# feedback.net
KiCad netlist of a schematic drawn in Altium Designer
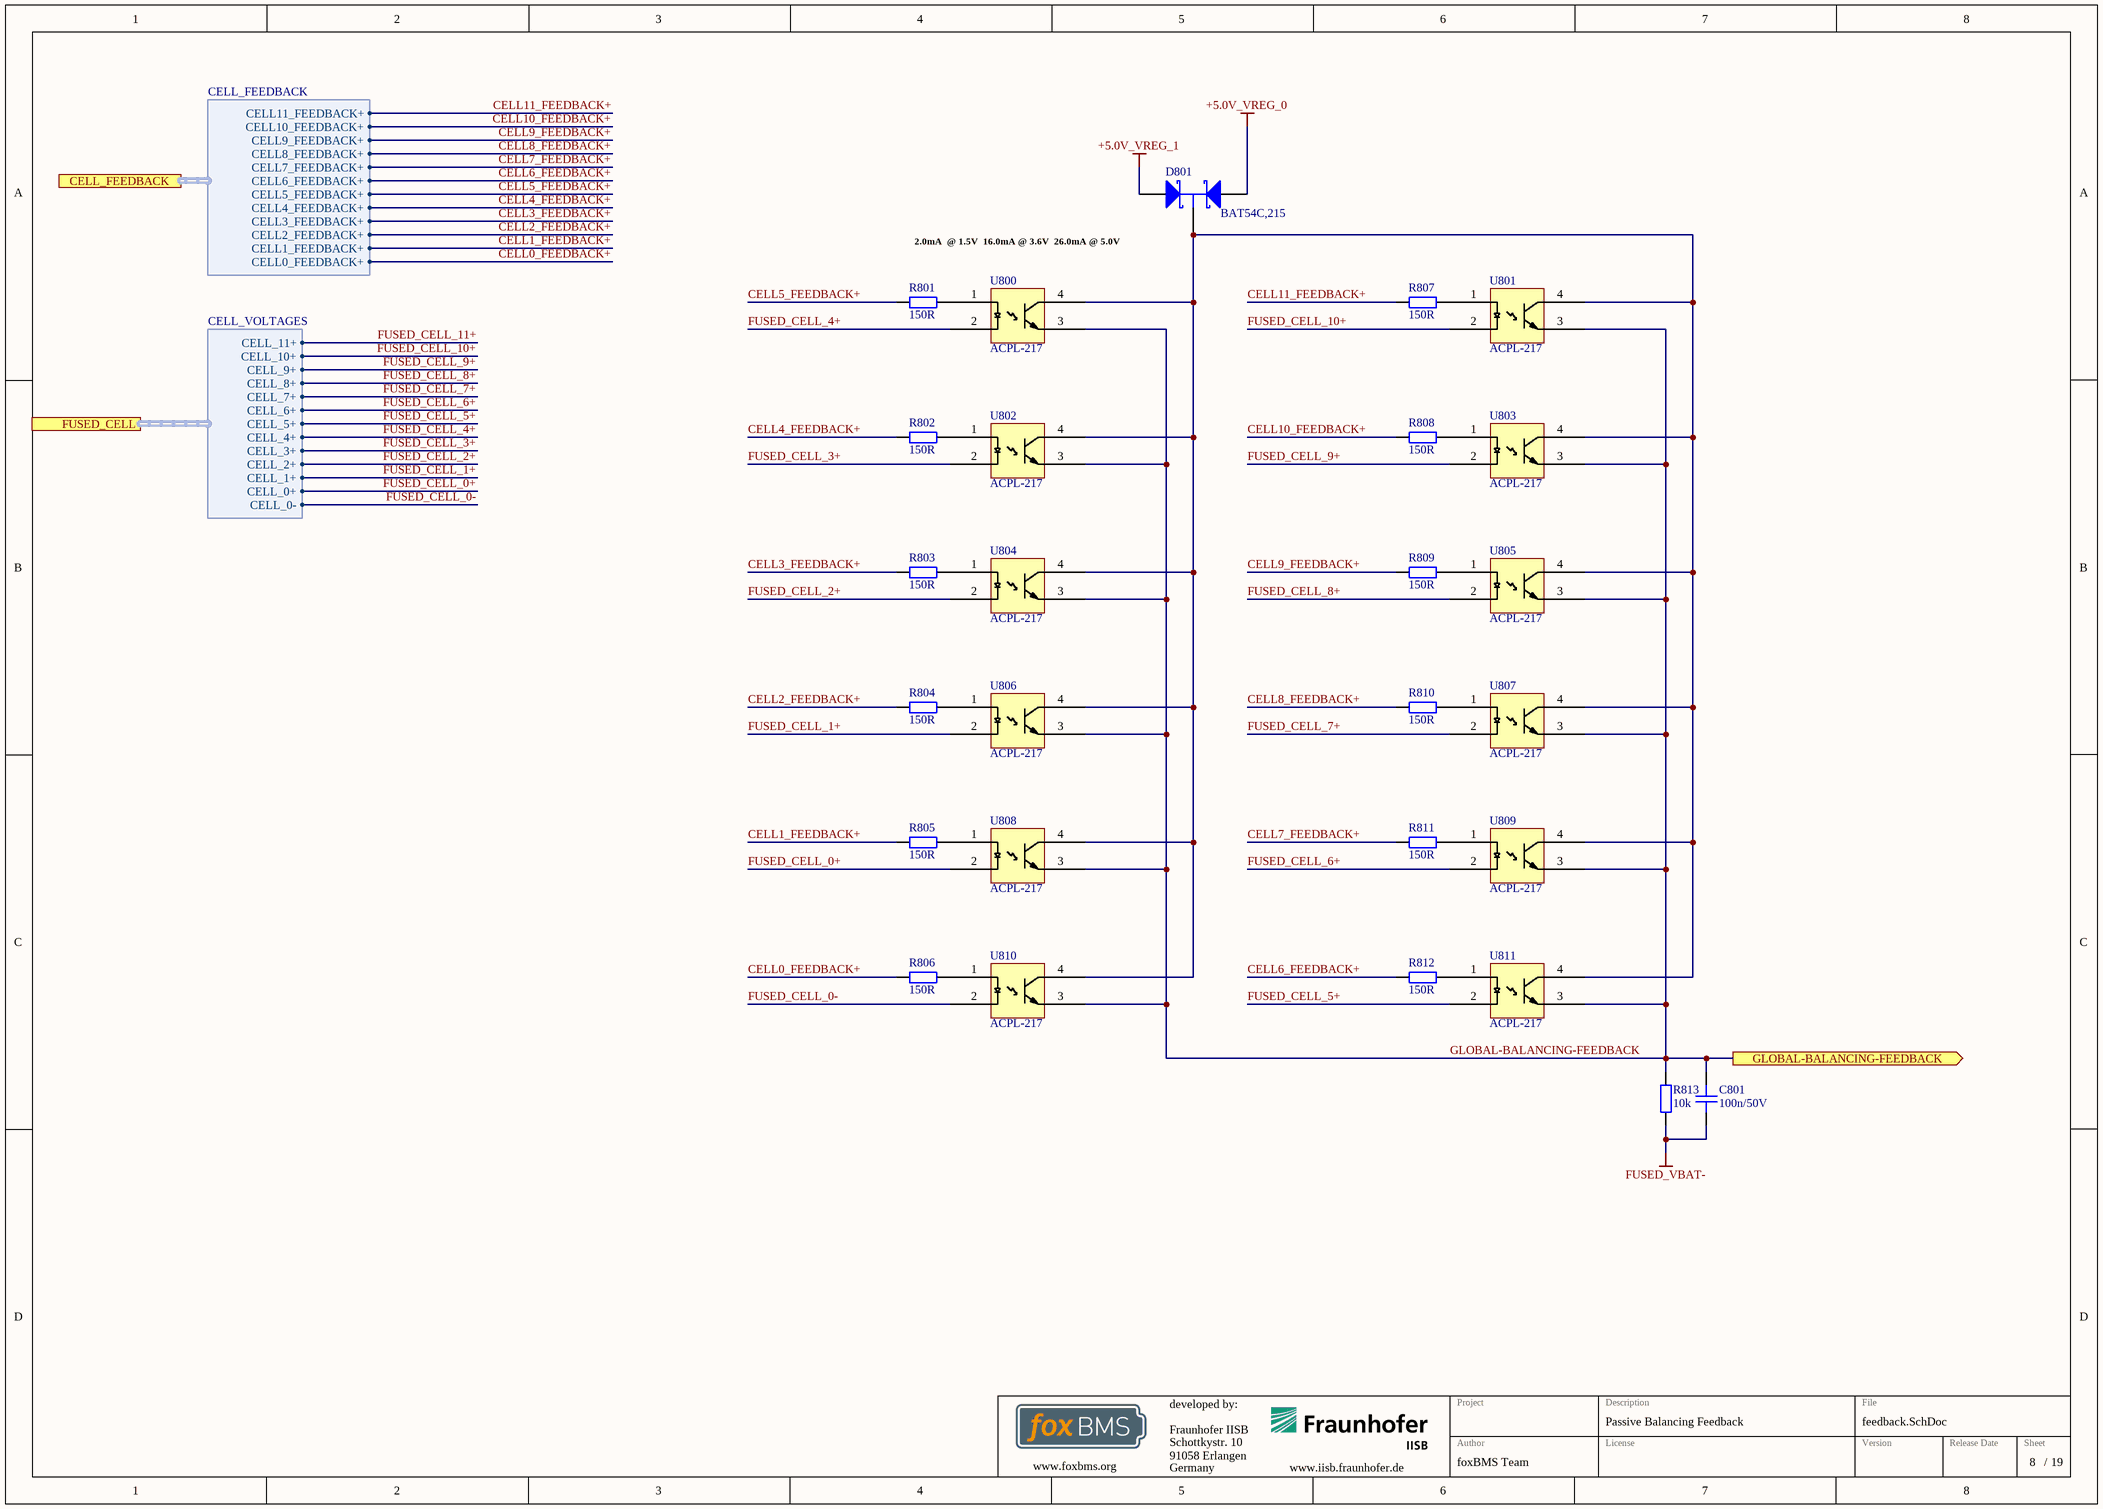
[diagram p0: feedback.SchDoc]

(export (version "E")
  (design (tool "Eeschema 10.0.6"))
  (components
    (comp (ref "C801")
      (value "100n/50V")
      (footprint "CAPC1608X08N")
      (description "MLCC")
      (fields (field (name "PART NUMBER") "gen_C_ceramic_100n_50V_X7R_0603"))
      (libsource (lib "OE750") (part "C"))
    )
    (comp (ref "D801")
      (value "BAT54C,215")
      (footprint "NXP-SOT23-3_V")
      (description "Schottky Barrier Diode, 30 V, 3-Pin SOT23, RoHS, Tape and Reel")
      (fields (field (name "MANUFACTURER") "NXP Semiconductors"))
      (libsource (lib "Altium Content Vault") (part "DSKY-AAK-3"))
    )
    (comp (ref "R801")
      (value "150R")
      (footprint "RESC1608X05N")
      (description "SMD Resistor 150R 0603")
      (fields (field (name "PART NUMBER") "gen_R_150R_0603") (field (name "TOLERANCE") "1%"))
      (libsource (lib "OE750") (part "R"))
    )
    (comp (ref "R802")
      (value "150R")
      (footprint "RESC1608X05N")
      (description "SMD Resistor 150R 0603")
      (fields (field (name "PART NUMBER") "gen_R_150R_0603") (field (name "TOLERANCE") "1%"))
      (libsource (lib "OE750") (part "R"))
    )
    (comp (ref "R803")
      (value "150R")
      (footprint "RESC1608X05N")
      (description "SMD Resistor 150R 0603")
      (fields (field (name "PART NUMBER") "gen_R_150R_0603") (field (name "TOLERANCE") "1%"))
      (libsource (lib "OE750") (part "R"))
    )
    (comp (ref "R804")
      (value "150R")
      (footprint "RESC1608X05N")
      (description "SMD Resistor 150R 0603")
      (fields (field (name "PART NUMBER") "gen_R_150R_0603") (field (name "TOLERANCE") "1%"))
      (libsource (lib "OE750") (part "R"))
    )
    (comp (ref "R805")
      (value "150R")
      (footprint "RESC1608X05N")
      (description "SMD Resistor 150R 0603")
      (fields (field (name "PART NUMBER") "gen_R_150R_0603") (field (name "TOLERANCE") "1%"))
      (libsource (lib "OE750") (part "R"))
    )
    (comp (ref "R806")
      (value "150R")
      (footprint "RESC1608X05N")
      (description "SMD Resistor 150R 0603")
      (fields (field (name "PART NUMBER") "gen_R_150R_0603") (field (name "TOLERANCE") "1%"))
      (libsource (lib "OE750") (part "R"))
    )
    (comp (ref "R807")
      (value "150R")
      (footprint "RESC1608X05N")
      (description "SMD Resistor 150R 0603")
      (fields (field (name "PART NUMBER") "gen_R_150R_0603") (field (name "TOLERANCE") "1%"))
      (libsource (lib "OE750") (part "R"))
    )
    (comp (ref "R808")
      (value "150R")
      (footprint "RESC1608X05N")
      (description "SMD Resistor 150R 0603")
      (fields (field (name "PART NUMBER") "gen_R_150R_0603") (field (name "TOLERANCE") "1%"))
      (libsource (lib "OE750") (part "R"))
    )
    (comp (ref "R809")
      (value "150R")
      (footprint "RESC1608X05N")
      (description "SMD Resistor 150R 0603")
      (fields (field (name "PART NUMBER") "gen_R_150R_0603") (field (name "TOLERANCE") "1%"))
      (libsource (lib "OE750") (part "R"))
    )
    (comp (ref "R810")
      (value "150R")
      (footprint "RESC1608X05N")
      (description "SMD Resistor 150R 0603")
      (fields (field (name "PART NUMBER") "gen_R_150R_0603") (field (name "TOLERANCE") "1%"))
      (libsource (lib "OE750") (part "R"))
    )
    (comp (ref "R811")
      (value "150R")
      (footprint "RESC1608X05N")
      (description "SMD Resistor 150R 0603")
      (fields (field (name "PART NUMBER") "gen_R_150R_0603") (field (name "TOLERANCE") "1%"))
      (libsource (lib "OE750") (part "R"))
    )
    (comp (ref "R812")
      (value "150R")
      (footprint "RESC1608X05N")
      (description "SMD Resistor 150R 0603")
      (fields (field (name "PART NUMBER") "gen_R_150R_0603") (field (name "TOLERANCE") "1%"))
      (libsource (lib "OE750") (part "R"))
    )
    (comp (ref "R813")
      (value "10k")
      (footprint "RESC1608X05N")
      (description "SMD Resistor 10k 0603")
      (fields (field (name "PART NUMBER") "gen_R_10k_0603") (field (name "TOLERANCE") "1%"))
      (libsource (lib "OE750") (part "R"))
    )
    (comp (ref "U800")
      (value "ACPL-217")
      (footprint "SOIC127P700X220-4N")
      (description "Optocoupler, Transistor Output, 1 Channel")
      (fields (field (name "PART NUMBER") "ACPL-217-56BE") (field (name "MANUFACTURER") "Broadcom Limited"))
      (libsource (lib "OE750") (part "ACPL-217"))
    )
    (comp (ref "U801")
      (value "ACPL-217")
      (footprint "SOIC127P700X220-4N")
      (description "Optocoupler, Transistor Output, 1 Channel")
      (fields (field (name "PART NUMBER") "ACPL-217-56BE") (field (name "MANUFACTURER") "Broadcom Limited"))
      (libsource (lib "OE750") (part "ACPL-217"))
    )
    (comp (ref "U802")
      (value "ACPL-217")
      (footprint "SOIC127P700X220-4N")
      (description "Optocoupler, Transistor Output, 1 Channel")
      (fields (field (name "PART NUMBER") "ACPL-217-56BE") (field (name "MANUFACTURER") "Broadcom Limited"))
      (libsource (lib "OE750") (part "ACPL-217"))
    )
    (comp (ref "U803")
      (value "ACPL-217")
      (footprint "SOIC127P700X220-4N")
      (description "Optocoupler, Transistor Output, 1 Channel")
      (fields (field (name "PART NUMBER") "ACPL-217-56BE") (field (name "MANUFACTURER") "Broadcom Limited"))
      (libsource (lib "OE750") (part "ACPL-217"))
    )
    (comp (ref "U804")
      (value "ACPL-217")
      (footprint "SOIC127P700X220-4N")
      (description "Optocoupler, Transistor Output, 1 Channel")
      (fields (field (name "PART NUMBER") "ACPL-217-56BE") (field (name "MANUFACTURER") "Broadcom Limited"))
      (libsource (lib "OE750") (part "ACPL-217"))
    )
    (comp (ref "U805")
      (value "ACPL-217")
      (footprint "SOIC127P700X220-4N")
      (description "Optocoupler, Transistor Output, 1 Channel")
      (fields (field (name "PART NUMBER") "ACPL-217-56BE") (field (name "MANUFACTURER") "Broadcom Limited"))
      (libsource (lib "OE750") (part "ACPL-217"))
    )
    (comp (ref "U806")
      (value "ACPL-217")
      (footprint "SOIC127P700X220-4N")
      (description "Optocoupler, Transistor Output, 1 Channel")
      (fields (field (name "PART NUMBER") "ACPL-217-56BE") (field (name "MANUFACTURER") "Broadcom Limited"))
      (libsource (lib "OE750") (part "ACPL-217"))
    )
    (comp (ref "U807")
      (value "ACPL-217")
      (footprint "SOIC127P700X220-4N")
      (description "Optocoupler, Transistor Output, 1 Channel")
      (fields (field (name "PART NUMBER") "ACPL-217-56BE") (field (name "MANUFACTURER") "Broadcom Limited"))
      (libsource (lib "OE750") (part "ACPL-217"))
    )
    (comp (ref "U808")
      (value "ACPL-217")
      (footprint "SOIC127P700X220-4N")
      (description "Optocoupler, Transistor Output, 1 Channel")
      (fields (field (name "PART NUMBER") "ACPL-217-56BE") (field (name "MANUFACTURER") "Broadcom Limited"))
      (libsource (lib "OE750") (part "ACPL-217"))
    )
    (comp (ref "U809")
      (value "ACPL-217")
      (footprint "SOIC127P700X220-4N")
      (description "Optocoupler, Transistor Output, 1 Channel")
      (fields (field (name "PART NUMBER") "ACPL-217-56BE") (field (name "MANUFACTURER") "Broadcom Limited"))
      (libsource (lib "OE750") (part "ACPL-217"))
    )
    (comp (ref "U810")
      (value "ACPL-217")
      (footprint "SOIC127P700X220-4N")
      (description "Optocoupler, Transistor Output, 1 Channel")
      (fields (field (name "PART NUMBER") "ACPL-217-56BE") (field (name "MANUFACTURER") "Broadcom Limited"))
      (libsource (lib "OE750") (part "ACPL-217"))
    )
    (comp (ref "U811")
      (value "ACPL-217")
      (footprint "SOIC127P700X220-4N")
      (description "Optocoupler, Transistor Output, 1 Channel")
      (fields (field (name "PART NUMBER") "ACPL-217-56BE") (field (name "MANUFACTURER") "Broadcom Limited"))
      (libsource (lib "OE750") (part "ACPL-217"))
    )
  )
  (nets
    (net (code "3") (name "+5.0V_VREG_0") (class "Default")
      (node (ref "D801") (pin "2") (pinfunction "A_2") (pintype "passive"))
    )
    (net (code "4") (name "+5.0V_VREG_1") (class "Default")
      (node (ref "D801") (pin "1") (pinfunction "A_1") (pintype "passive"))
    )
    (net (code "5") (name "/CELL0_FEEDBACK+") (class "Default")
      (node (ref "R806") (pin "1") (pinfunction "1_1") (pintype "passive"))
    )
    (net (code "6") (name "/CELL1_FEEDBACK+") (class "Default")
      (node (ref "R805") (pin "1") (pinfunction "1_1") (pintype "passive"))
    )
    (net (code "7") (name "/CELL2_FEEDBACK+") (class "Default")
      (node (ref "R804") (pin "1") (pinfunction "1_1") (pintype "passive"))
    )
    (net (code "8") (name "/CELL3_FEEDBACK+") (class "Default")
      (node (ref "R803") (pin "1") (pinfunction "1_1") (pintype "passive"))
    )
    (net (code "9") (name "/CELL4_FEEDBACK+") (class "Default")
      (node (ref "R802") (pin "1") (pinfunction "1_1") (pintype "passive"))
    )
    (net (code "10") (name "/CELL5_FEEDBACK+") (class "Default")
      (node (ref "R801") (pin "1") (pinfunction "1_1") (pintype "passive"))
    )
    (net (code "11") (name "/CELL6_FEEDBACK+") (class "Default")
      (node (ref "R812") (pin "1") (pinfunction "1_1") (pintype "passive"))
    )
    (net (code "12") (name "/CELL7_FEEDBACK+") (class "Default")
      (node (ref "R811") (pin "1") (pinfunction "1_1") (pintype "passive"))
    )
    (net (code "13") (name "/CELL8_FEEDBACK+") (class "Default")
      (node (ref "R810") (pin "1") (pinfunction "1_1") (pintype "passive"))
    )
    (net (code "14") (name "/CELL9_FEEDBACK+") (class "Default")
      (node (ref "R809") (pin "1") (pinfunction "1_1") (pintype "passive"))
    )
    (net (code "15") (name "/CELL10_FEEDBACK+") (class "Default")
      (node (ref "R808") (pin "1") (pinfunction "1_1") (pintype "passive"))
    )
    (net (code "16") (name "/CELL11_FEEDBACK+") (class "Default")
      (node (ref "R807") (pin "1") (pinfunction "1_1") (pintype "passive"))
    )
    (net (code "17") (name "/FUSED_CELL_0+") (class "Default")
      (node (ref "U808") (pin "2") (pintype "power_in"))
    )
    (net (code "18") (name "/FUSED_CELL_0-") (class "Default")
      (node (ref "U810") (pin "2") (pintype "power_in"))
    )
    (net (code "19") (name "/FUSED_CELL_1+") (class "Default")
      (node (ref "U806") (pin "2") (pintype "power_in"))
    )
    (net (code "20") (name "/FUSED_CELL_2+") (class "Default")
      (node (ref "U804") (pin "2") (pintype "power_in"))
    )
    (net (code "21") (name "/FUSED_CELL_3+") (class "Default")
      (node (ref "U802") (pin "2") (pintype "power_in"))
    )
    (net (code "22") (name "/FUSED_CELL_4+") (class "Default")
      (node (ref "U800") (pin "2") (pintype "power_in"))
    )
    (net (code "23") (name "/FUSED_CELL_5+") (class "Default")
      (node (ref "U811") (pin "2") (pintype "power_in"))
    )
    (net (code "24") (name "/FUSED_CELL_6+") (class "Default")
      (node (ref "U809") (pin "2") (pintype "power_in"))
    )
    (net (code "25") (name "/FUSED_CELL_7+") (class "Default")
      (node (ref "U807") (pin "2") (pintype "power_in"))
    )
    (net (code "26") (name "/FUSED_CELL_8+") (class "Default")
      (node (ref "U805") (pin "2") (pintype "power_in"))
    )
    (net (code "27") (name "/FUSED_CELL_9+") (class "Default")
      (node (ref "U803") (pin "2") (pintype "power_in"))
    )
    (net (code "28") (name "/FUSED_CELL_10+") (class "Default")
      (node (ref "U801") (pin "2") (pintype "power_in"))
    )
    (net (code "30") (name "/GLOBAL-BALANCING-FEEDBACK") (class "Default")
      (node (ref "C801") (pin "2") (pinfunction "2_2") (pintype "passive"))
      (node (ref "R813") (pin "1") (pinfunction "1_1") (pintype "passive"))
      (node (ref "U800") (pin "3") (pintype "passive"))
      (node (ref "U801") (pin "3") (pintype "passive"))
      (node (ref "U802") (pin "3") (pintype "passive"))
      (node (ref "U803") (pin "3") (pintype "passive"))
      (node (ref "U804") (pin "3") (pintype "passive"))
      (node (ref "U805") (pin "3") (pintype "passive"))
      (node (ref "U806") (pin "3") (pintype "passive"))
      (node (ref "U807") (pin "3") (pintype "passive"))
      (node (ref "U808") (pin "3") (pintype "passive"))
      (node (ref "U809") (pin "3") (pintype "passive"))
      (node (ref "U810") (pin "3") (pintype "passive"))
      (node (ref "U811") (pin "3") (pintype "passive"))
    )
    (net (code "33") (name "FUSED_VBAT-") (class "Default")
      (node (ref "C801") (pin "1") (pinfunction "1_1") (pintype "passive"))
      (node (ref "R813") (pin "2") (pinfunction "2_2") (pintype "passive"))
    )
    (net (code "34") (name "Net-(D801-K)") (class "Default")
      (node (ref "D801") (pin "3") (pinfunction "K_3") (pintype "passive"))
      (node (ref "U800") (pin "4") (pintype "passive"))
      (node (ref "U801") (pin "4") (pintype "passive"))
      (node (ref "U802") (pin "4") (pintype "passive"))
      (node (ref "U803") (pin "4") (pintype "passive"))
      (node (ref "U804") (pin "4") (pintype "passive"))
      (node (ref "U805") (pin "4") (pintype "passive"))
      (node (ref "U806") (pin "4") (pintype "passive"))
      (node (ref "U807") (pin "4") (pintype "passive"))
      (node (ref "U808") (pin "4") (pintype "passive"))
      (node (ref "U809") (pin "4") (pintype "passive"))
      (node (ref "U810") (pin "4") (pintype "passive"))
      (node (ref "U811") (pin "4") (pintype "passive"))
    )
    (net (code "35") (name "Net-(R801-Pad2)") (class "Default")
      (node (ref "R801") (pin "2") (pinfunction "2_2") (pintype "passive"))
      (node (ref "U800") (pin "1") (pintype "passive"))
    )
    (net (code "36") (name "Net-(R802-Pad2)") (class "Default")
      (node (ref "R802") (pin "2") (pinfunction "2_2") (pintype "passive"))
      (node (ref "U802") (pin "1") (pintype "passive"))
    )
    (net (code "37") (name "Net-(R803-Pad2)") (class "Default")
      (node (ref "R803") (pin "2") (pinfunction "2_2") (pintype "passive"))
      (node (ref "U804") (pin "1") (pintype "passive"))
    )
    (net (code "38") (name "Net-(R804-Pad2)") (class "Default")
      (node (ref "R804") (pin "2") (pinfunction "2_2") (pintype "passive"))
      (node (ref "U806") (pin "1") (pintype "passive"))
    )
    (net (code "39") (name "Net-(R805-Pad2)") (class "Default")
      (node (ref "R805") (pin "2") (pinfunction "2_2") (pintype "passive"))
      (node (ref "U808") (pin "1") (pintype "passive"))
    )
    (net (code "40") (name "Net-(R806-Pad2)") (class "Default")
      (node (ref "R806") (pin "2") (pinfunction "2_2") (pintype "passive"))
      (node (ref "U810") (pin "1") (pintype "passive"))
    )
    (net (code "41") (name "Net-(R807-Pad2)") (class "Default")
      (node (ref "R807") (pin "2") (pinfunction "2_2") (pintype "passive"))
      (node (ref "U801") (pin "1") (pintype "passive"))
    )
    (net (code "42") (name "Net-(R808-Pad2)") (class "Default")
      (node (ref "R808") (pin "2") (pinfunction "2_2") (pintype "passive"))
      (node (ref "U803") (pin "1") (pintype "passive"))
    )
    (net (code "43") (name "Net-(R809-Pad2)") (class "Default")
      (node (ref "R809") (pin "2") (pinfunction "2_2") (pintype "passive"))
      (node (ref "U805") (pin "1") (pintype "passive"))
    )
    (net (code "44") (name "Net-(R810-Pad2)") (class "Default")
      (node (ref "R810") (pin "2") (pinfunction "2_2") (pintype "passive"))
      (node (ref "U807") (pin "1") (pintype "passive"))
    )
    (net (code "45") (name "Net-(R811-Pad2)") (class "Default")
      (node (ref "R811") (pin "2") (pinfunction "2_2") (pintype "passive"))
      (node (ref "U809") (pin "1") (pintype "passive"))
    )
    (net (code "46") (name "Net-(R812-Pad2)") (class "Default")
      (node (ref "R812") (pin "2") (pinfunction "2_2") (pintype "passive"))
      (node (ref "U811") (pin "1") (pintype "passive"))
    )
  )
)
